# panel-8-touch-pad.net
KiCad netlist of a schematic drawn in Altium Designer
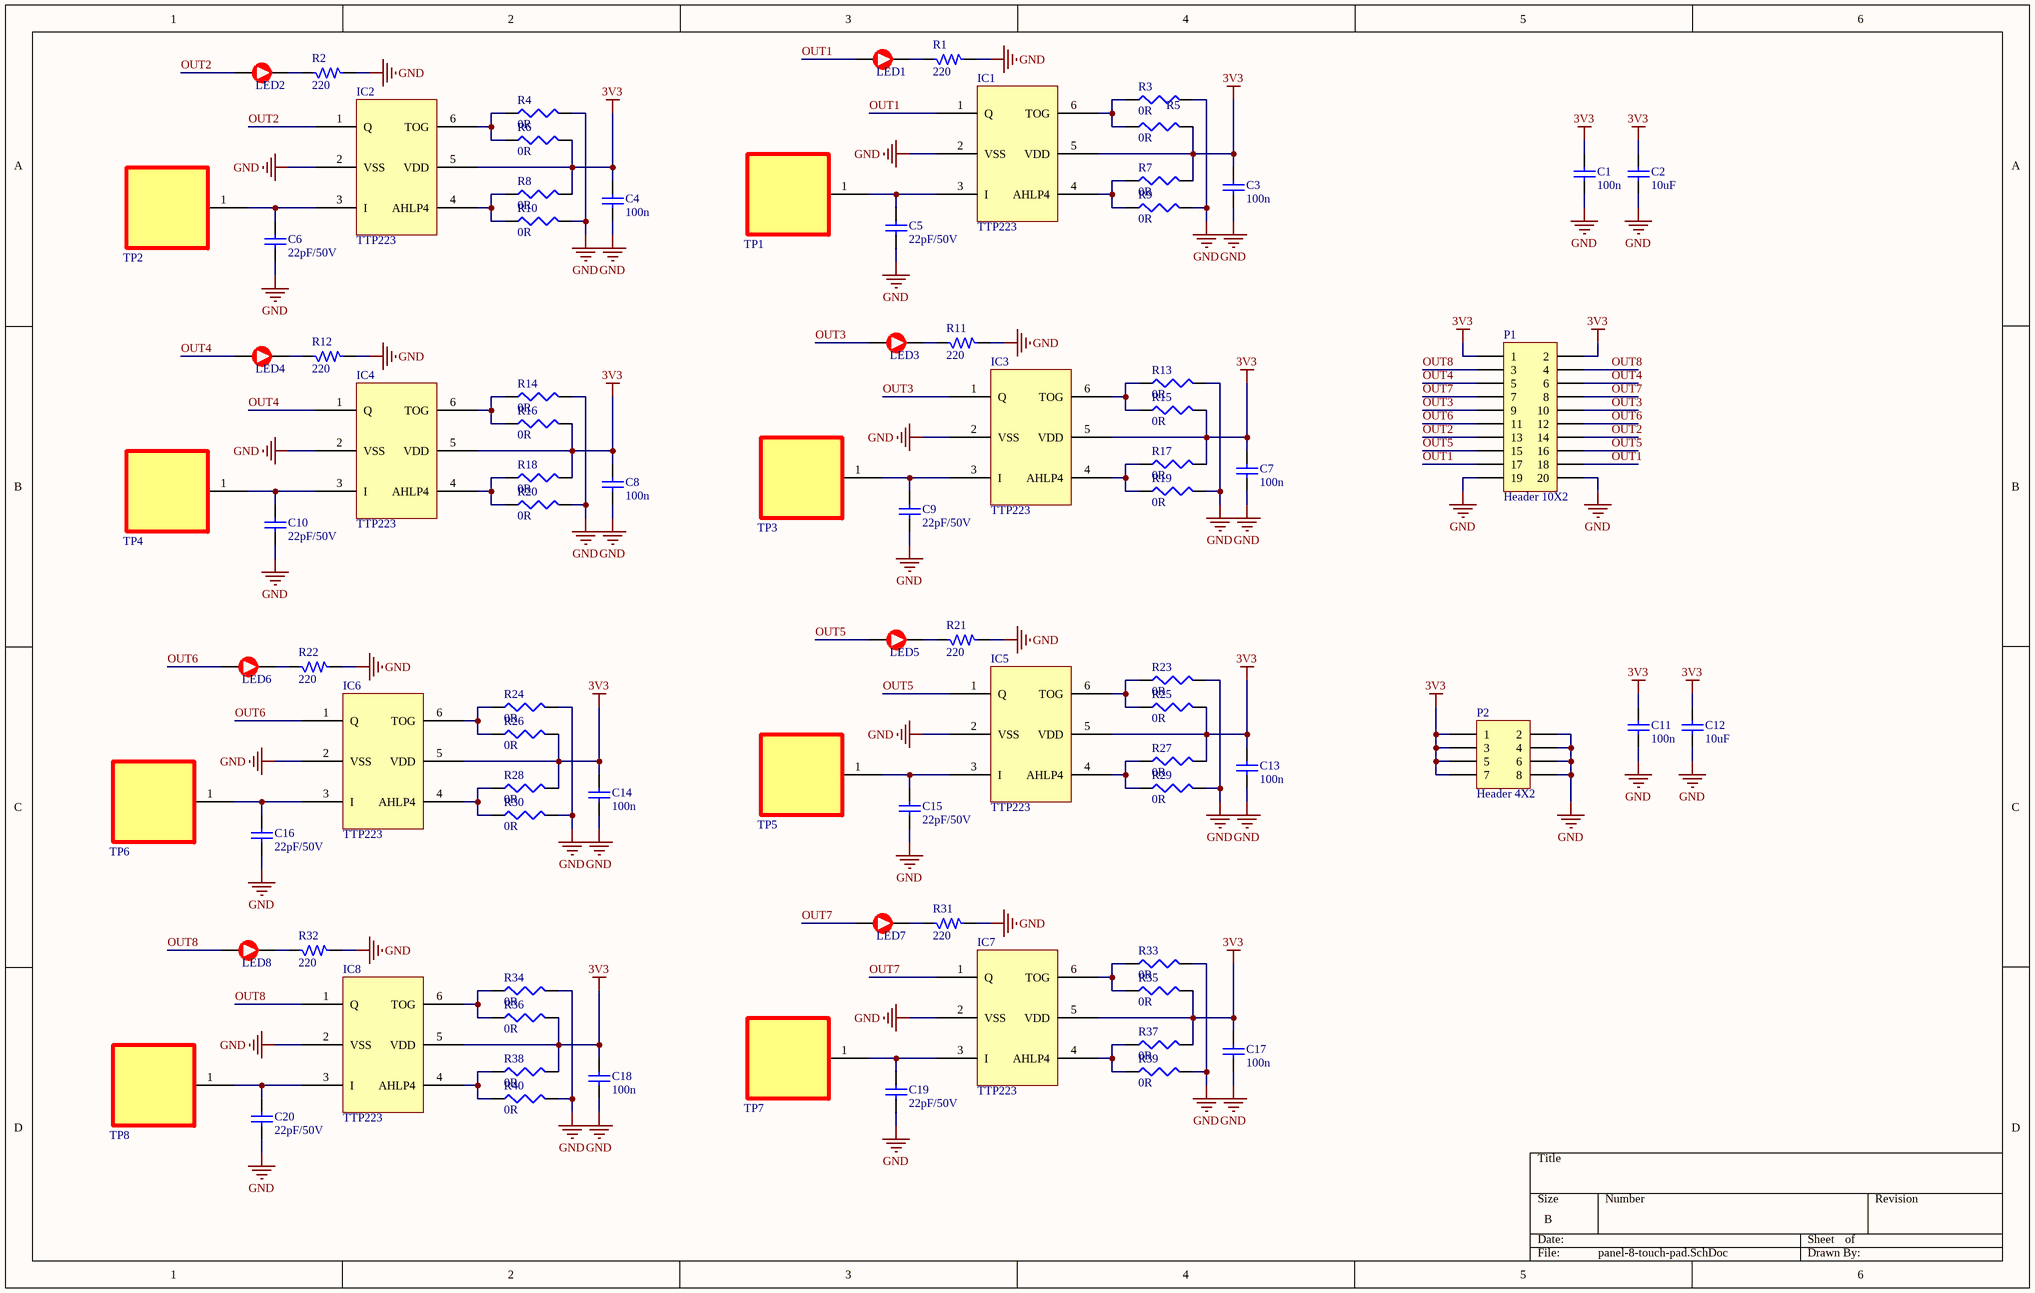
[diagram p0: panel-8-touch-pad.SchDoc]

(export (version "E")
  (design (tool "Eeschema 10.0.6"))
  (components
    (comp (ref "C1")
      (value "100n")
      (footprint "Capacitor:C0805")
      (description "Capacitor 100n 16V 0603")
      (fields (field (name "PUBLISHER") "Altium Limited"))
      (libsource (lib "Schlib1") (part "Cap Semi"))
    )
    (comp (ref "C2")
      (value "10uF")
      (footprint "Capacitor:C1206")
      (description "Capacitor 100n 16V 0603")
      (fields (field (name "PUBLISHER") "Altium Limited"))
      (libsource (lib "Schlib1") (part "Cap Semi"))
    )
    (comp (ref "C3")
      (value "100n")
      (footprint "Capacitor:C0805")
      (description "Capacitor 100n 16V 0603")
      (fields (field (name "PUBLISHER") "Altium Limited"))
      (libsource (lib "Schlib1") (part "Cap Semi"))
    )
    (comp (ref "C4")
      (value "100n")
      (footprint "Capacitor:C0805")
      (description "Capacitor 100n 16V 0603")
      (fields (field (name "PUBLISHER") "Altium Limited"))
      (libsource (lib "Schlib1") (part "Cap Semi"))
    )
    (comp (ref "C5")
      (value "22pF/50V")
      (footprint "Capacitor:C0805")
      (description "Capacitor 100n 16V 0603")
      (fields (field (name "PUBLISHER") "Altium Limited"))
      (libsource (lib "Schlib1") (part "Cap Semi"))
    )
    (comp (ref "C6")
      (value "22pF/50V")
      (footprint "Capacitor:C0805")
      (description "Capacitor 100n 16V 0603")
      (fields (field (name "PUBLISHER") "Altium Limited"))
      (libsource (lib "Schlib1") (part "Cap Semi"))
    )
    (comp (ref "C7")
      (value "100n")
      (footprint "Capacitor:C0805")
      (description "Capacitor 100n 16V 0603")
      (fields (field (name "PUBLISHER") "Altium Limited"))
      (libsource (lib "Schlib1") (part "Cap Semi"))
    )
    (comp (ref "C8")
      (value "100n")
      (footprint "Capacitor:C0805")
      (description "Capacitor 100n 16V 0603")
      (fields (field (name "PUBLISHER") "Altium Limited"))
      (libsource (lib "Schlib1") (part "Cap Semi"))
    )
    (comp (ref "C9")
      (value "22pF/50V")
      (footprint "Capacitor:C0805")
      (description "Capacitor 100n 16V 0603")
      (fields (field (name "PUBLISHER") "Altium Limited"))
      (libsource (lib "Schlib1") (part "Cap Semi"))
    )
    (comp (ref "C10")
      (value "22pF/50V")
      (footprint "Capacitor:C0805")
      (description "Capacitor 100n 16V 0603")
      (fields (field (name "PUBLISHER") "Altium Limited"))
      (libsource (lib "Schlib1") (part "Cap Semi"))
    )
    (comp (ref "C11")
      (value "100n")
      (footprint "Capacitor:C0805")
      (description "Capacitor 100n 16V 0603")
      (fields (field (name "PUBLISHER") "Altium Limited"))
      (libsource (lib "Schlib1") (part "Cap Semi"))
    )
    (comp (ref "C12")
      (value "10uF")
      (footprint "Capacitor:C1206")
      (description "Capacitor 100n 16V 0603")
      (fields (field (name "PUBLISHER") "Altium Limited"))
      (libsource (lib "Schlib1") (part "Cap Semi"))
    )
    (comp (ref "C13")
      (value "100n")
      (footprint "Capacitor:C0805")
      (description "Capacitor 100n 16V 0603")
      (fields (field (name "PUBLISHER") "Altium Limited"))
      (libsource (lib "Schlib1") (part "Cap Semi"))
    )
    (comp (ref "C14")
      (value "100n")
      (footprint "Capacitor:C0805")
      (description "Capacitor 100n 16V 0603")
      (fields (field (name "PUBLISHER") "Altium Limited"))
      (libsource (lib "Schlib1") (part "Cap Semi"))
    )
    (comp (ref "C15")
      (value "22pF/50V")
      (footprint "Capacitor:C0805")
      (description "Capacitor 100n 16V 0603")
      (fields (field (name "PUBLISHER") "Altium Limited"))
      (libsource (lib "Schlib1") (part "Cap Semi"))
    )
    (comp (ref "C16")
      (value "22pF/50V")
      (footprint "Capacitor:C0805")
      (description "Capacitor 100n 16V 0603")
      (fields (field (name "PUBLISHER") "Altium Limited"))
      (libsource (lib "Schlib1") (part "Cap Semi"))
    )
    (comp (ref "C17")
      (value "100n")
      (footprint "Capacitor:C0805")
      (description "Capacitor 100n 16V 0603")
      (fields (field (name "PUBLISHER") "Altium Limited"))
      (libsource (lib "Schlib1") (part "Cap Semi"))
    )
    (comp (ref "C18")
      (value "100n")
      (footprint "Capacitor:C0805")
      (description "Capacitor 100n 16V 0603")
      (fields (field (name "PUBLISHER") "Altium Limited"))
      (libsource (lib "Schlib1") (part "Cap Semi"))
    )
    (comp (ref "C19")
      (value "22pF/50V")
      (footprint "Capacitor:C0805")
      (description "Capacitor 100n 16V 0603")
      (fields (field (name "PUBLISHER") "Altium Limited"))
      (libsource (lib "Schlib1") (part "Cap Semi"))
    )
    (comp (ref "C20")
      (value "22pF/50V")
      (footprint "Capacitor:C0805")
      (description "Capacitor 100n 16V 0603")
      (fields (field (name "PUBLISHER") "Altium Limited"))
      (libsource (lib "Schlib1") (part "Cap Semi"))
    )
    (comp (ref "IC1")
      (value "TTP223")
      (footprint "Miscellaneous Devices:SOT23-6_L")
      (description "TTP223 Touch")
      (libsource (lib "touch-lib") (part "TTP223"))
    )
    (comp (ref "IC2")
      (value "TTP223")
      (footprint "Miscellaneous Devices:SOT23-6_L")
      (description "TTP223 Touch")
      (libsource (lib "touch-lib") (part "TTP223"))
    )
    (comp (ref "IC3")
      (value "TTP223")
      (footprint "Miscellaneous Devices:SOT23-6_L")
      (description "TTP223 Touch")
      (libsource (lib "touch-lib") (part "TTP223"))
    )
    (comp (ref "IC4")
      (value "TTP223")
      (footprint "Miscellaneous Devices:SOT23-6_L")
      (description "TTP223 Touch")
      (libsource (lib "touch-lib") (part "TTP223"))
    )
    (comp (ref "IC5")
      (value "TTP223")
      (footprint "Miscellaneous Devices:SOT23-6_L")
      (description "TTP223 Touch")
      (libsource (lib "touch-lib") (part "TTP223"))
    )
    (comp (ref "IC6")
      (value "TTP223")
      (footprint "Miscellaneous Devices:SOT23-6_L")
      (description "TTP223 Touch")
      (libsource (lib "touch-lib") (part "TTP223"))
    )
    (comp (ref "IC7")
      (value "TTP223")
      (footprint "Miscellaneous Devices:SOT23-6_L")
      (description "TTP223 Touch")
      (libsource (lib "touch-lib") (part "TTP223"))
    )
    (comp (ref "IC8")
      (value "TTP223")
      (footprint "Miscellaneous Devices:SOT23-6_L")
      (description "TTP223 Touch")
      (libsource (lib "touch-lib") (part "TTP223"))
    )
    (comp (ref "LED1")
      (value "led-lib:LED_0805_Blue")
      (footprint "led-lib:LED_0805_Blue")
      (description "LED")
      (fields (field (name "MANUFACTURER") "Harvatek"))
      (libsource (lib "SS_Basic") (part "Led"))
    )
    (comp (ref "LED2")
      (value "led-lib:LED_0805_Blue")
      (footprint "led-lib:LED_0805_Blue")
      (description "LED")
      (fields (field (name "MANUFACTURER") "Harvatek"))
      (libsource (lib "SS_Basic") (part "Led"))
    )
    (comp (ref "LED3")
      (value "led-lib:LED_0805_Blue")
      (footprint "led-lib:LED_0805_Blue")
      (description "LED")
      (fields (field (name "MANUFACTURER") "Harvatek"))
      (libsource (lib "SS_Basic") (part "Led"))
    )
    (comp (ref "LED4")
      (value "led-lib:LED_0805_Blue")
      (footprint "led-lib:LED_0805_Blue")
      (description "LED")
      (fields (field (name "MANUFACTURER") "Harvatek"))
      (libsource (lib "SS_Basic") (part "Led"))
    )
    (comp (ref "LED5")
      (value "led-lib:LED_0805_Blue")
      (footprint "led-lib:LED_0805_Blue")
      (description "LED")
      (fields (field (name "MANUFACTURER") "Harvatek"))
      (libsource (lib "SS_Basic") (part "Led"))
    )
    (comp (ref "LED6")
      (value "led-lib:LED_0805_Blue")
      (footprint "led-lib:LED_0805_Blue")
      (description "LED")
      (fields (field (name "MANUFACTURER") "Harvatek"))
      (libsource (lib "SS_Basic") (part "Led"))
    )
    (comp (ref "LED7")
      (value "led-lib:LED_0805_Blue")
      (footprint "led-lib:LED_0805_Blue")
      (description "LED")
      (fields (field (name "MANUFACTURER") "Harvatek"))
      (libsource (lib "SS_Basic") (part "Led"))
    )
    (comp (ref "LED8")
      (value "led-lib:LED_0805_Blue")
      (footprint "led-lib:LED_0805_Blue")
      (description "LED")
      (fields (field (name "MANUFACTURER") "Harvatek"))
      (libsource (lib "SS_Basic") (part "Led"))
    )
    (comp (ref "P1")
      (value "Header 10X2")
      (footprint "SS_Con:HDR2X10 - SMD - 2mm")
      (description "Header, 10-Pin, Dual row")
      (fields (field (name "PUBLISHER") "Altium Limited"))
      (libsource (lib "SS_Con") (part "Header 10X2"))
    )
    (comp (ref "P2")
      (value "Header 4X2")
      (footprint "SS_Con:HDR2X4 - SMD - 2mm")
      (description "Header, 4-Pin, Dual row")
      (fields (field (name "PUBLISHER") "Altium Limited"))
      (libsource (lib "SS_Con") (part "Header 4X2"))
    )
    (comp (ref "R1")
      (value "220")
      (footprint "R0805")
      (description "Resistor SMD")
      (fields (field (name "MANUFACTURER") "UniOhm"))
      (libsource (lib "Schlib1") (part "RM"))
    )
    (comp (ref "R2")
      (value "220")
      (footprint "R0805")
      (description "Resistor SMD")
      (fields (field (name "MANUFACTURER") "UniOhm"))
      (libsource (lib "Schlib1") (part "RM"))
    )
    (comp (ref "R3")
      (value "0R")
      (footprint "R0805")
      (description "Resistor 10k 0603")
      (fields (field (name "PUBLISHER") "Altium Limited"))
      (libsource (lib "Miscellaneous Devices") (part "Res3"))
    )
    (comp (ref "R4")
      (value "0R")
      (footprint "R0805")
      (description "Resistor 10k 0603")
      (fields (field (name "PUBLISHER") "Altium Limited"))
      (libsource (lib "Miscellaneous Devices") (part "Res3"))
    )
    (comp (ref "R5")
      (value "0R")
      (footprint "R0805")
      (description "Resistor 10k 0603")
      (fields (field (name "PUBLISHER") "Altium Limited"))
      (libsource (lib "Miscellaneous Devices") (part "Res3"))
    )
    (comp (ref "R6")
      (value "0R")
      (footprint "R0805")
      (description "Resistor 10k 0603")
      (fields (field (name "PUBLISHER") "Altium Limited"))
      (libsource (lib "Miscellaneous Devices") (part "Res3"))
    )
    (comp (ref "R7")
      (value "0R")
      (footprint "R0805")
      (description "Resistor 10k 0603")
      (fields (field (name "PUBLISHER") "Altium Limited"))
      (libsource (lib "Miscellaneous Devices") (part "Res3"))
    )
    (comp (ref "R8")
      (value "0R")
      (footprint "R0805")
      (description "Resistor 10k 0603")
      (fields (field (name "PUBLISHER") "Altium Limited"))
      (libsource (lib "Miscellaneous Devices") (part "Res3"))
    )
    (comp (ref "R9")
      (value "0R")
      (footprint "R0805")
      (description "Resistor 10k 0603")
      (fields (field (name "PUBLISHER") "Altium Limited"))
      (libsource (lib "Miscellaneous Devices") (part "Res3"))
    )
    (comp (ref "R10")
      (value "0R")
      (footprint "R0805")
      (description "Resistor 10k 0603")
      (fields (field (name "PUBLISHER") "Altium Limited"))
      (libsource (lib "Miscellaneous Devices") (part "Res3"))
    )
    (comp (ref "R11")
      (value "220")
      (footprint "R0805")
      (description "Resistor SMD")
      (fields (field (name "MANUFACTURER") "UniOhm"))
      (libsource (lib "Schlib1") (part "RM"))
    )
    (comp (ref "R12")
      (value "220")
      (footprint "R0805")
      (description "Resistor SMD")
      (fields (field (name "MANUFACTURER") "UniOhm"))
      (libsource (lib "Schlib1") (part "RM"))
    )
    (comp (ref "R13")
      (value "0R")
      (footprint "R0805")
      (description "Resistor 10k 0603")
      (fields (field (name "PUBLISHER") "Altium Limited"))
      (libsource (lib "Miscellaneous Devices") (part "Res3"))
    )
    (comp (ref "R14")
      (value "0R")
      (footprint "R0805")
      (description "Resistor 10k 0603")
      (fields (field (name "PUBLISHER") "Altium Limited"))
      (libsource (lib "Miscellaneous Devices") (part "Res3"))
    )
    (comp (ref "R15")
      (value "0R")
      (footprint "R0805")
      (description "Resistor 10k 0603")
      (fields (field (name "PUBLISHER") "Altium Limited"))
      (libsource (lib "Miscellaneous Devices") (part "Res3"))
    )
    (comp (ref "R16")
      (value "0R")
      (footprint "R0805")
      (description "Resistor 10k 0603")
      (fields (field (name "PUBLISHER") "Altium Limited"))
      (libsource (lib "Miscellaneous Devices") (part "Res3"))
    )
    (comp (ref "R17")
      (value "0R")
      (footprint "R0805")
      (description "Resistor 10k 0603")
      (fields (field (name "PUBLISHER") "Altium Limited"))
      (libsource (lib "Miscellaneous Devices") (part "Res3"))
    )
    (comp (ref "R18")
      (value "0R")
      (footprint "R0805")
      (description "Resistor 10k 0603")
      (fields (field (name "PUBLISHER") "Altium Limited"))
      (libsource (lib "Miscellaneous Devices") (part "Res3"))
    )
    (comp (ref "R19")
      (value "0R")
      (footprint "R0805")
      (description "Resistor 10k 0603")
      (fields (field (name "PUBLISHER") "Altium Limited"))
      (libsource (lib "Miscellaneous Devices") (part "Res3"))
    )
    (comp (ref "R20")
      (value "0R")
      (footprint "R0805")
      (description "Resistor 10k 0603")
      (fields (field (name "PUBLISHER") "Altium Limited"))
      (libsource (lib "Miscellaneous Devices") (part "Res3"))
    )
    (comp (ref "R21")
      (value "220")
      (footprint "R0805")
      (description "Resistor SMD")
      (fields (field (name "MANUFACTURER") "UniOhm"))
      (libsource (lib "Schlib1") (part "RM"))
    )
    (comp (ref "R22")
      (value "220")
      (footprint "R0805")
      (description "Resistor SMD")
      (fields (field (name "MANUFACTURER") "UniOhm"))
      (libsource (lib "Schlib1") (part "RM"))
    )
    (comp (ref "R23")
      (value "0R")
      (footprint "R0805")
      (description "Resistor 10k 0603")
      (fields (field (name "PUBLISHER") "Altium Limited"))
      (libsource (lib "Miscellaneous Devices") (part "Res3"))
    )
    (comp (ref "R24")
      (value "0R")
      (footprint "R0805")
      (description "Resistor 10k 0603")
      (fields (field (name "PUBLISHER") "Altium Limited"))
      (libsource (lib "Miscellaneous Devices") (part "Res3"))
    )
    (comp (ref "R25")
      (value "0R")
      (footprint "R0805")
      (description "Resistor 10k 0603")
      (fields (field (name "PUBLISHER") "Altium Limited"))
      (libsource (lib "Miscellaneous Devices") (part "Res3"))
    )
    (comp (ref "R26")
      (value "0R")
      (footprint "R0805")
      (description "Resistor 10k 0603")
      (fields (field (name "PUBLISHER") "Altium Limited"))
      (libsource (lib "Miscellaneous Devices") (part "Res3"))
    )
    (comp (ref "R27")
      (value "0R")
      (footprint "R0805")
      (description "Resistor 10k 0603")
      (fields (field (name "PUBLISHER") "Altium Limited"))
      (libsource (lib "Miscellaneous Devices") (part "Res3"))
    )
    (comp (ref "R28")
      (value "0R")
      (footprint "R0805")
      (description "Resistor 10k 0603")
      (fields (field (name "PUBLISHER") "Altium Limited"))
      (libsource (lib "Miscellaneous Devices") (part "Res3"))
    )
    (comp (ref "R29")
      (value "0R")
      (footprint "R0805")
      (description "Resistor 10k 0603")
      (fields (field (name "PUBLISHER") "Altium Limited"))
      (libsource (lib "Miscellaneous Devices") (part "Res3"))
    )
    (comp (ref "R30")
      (value "0R")
      (footprint "R0805")
      (description "Resistor 10k 0603")
      (fields (field (name "PUBLISHER") "Altium Limited"))
      (libsource (lib "Miscellaneous Devices") (part "Res3"))
    )
    (comp (ref "R31")
      (value "220")
      (footprint "R0805")
      (description "Resistor SMD")
      (fields (field (name "MANUFACTURER") "UniOhm"))
      (libsource (lib "Schlib1") (part "RM"))
    )
    (comp (ref "R32")
      (value "220")
      (footprint "R0805")
      (description "Resistor SMD")
      (fields (field (name "MANUFACTURER") "UniOhm"))
      (libsource (lib "Schlib1") (part "RM"))
    )
    (comp (ref "R33")
      (value "0R")
      (footprint "R0805")
      (description "Resistor 10k 0603")
      (fields (field (name "PUBLISHER") "Altium Limited"))
      (libsource (lib "Miscellaneous Devices") (part "Res3"))
    )
    (comp (ref "R34")
      (value "0R")
      (footprint "R0805")
      (description "Resistor 10k 0603")
      (fields (field (name "PUBLISHER") "Altium Limited"))
      (libsource (lib "Miscellaneous Devices") (part "Res3"))
    )
    (comp (ref "R35")
      (value "0R")
      (footprint "R0805")
      (description "Resistor 10k 0603")
      (fields (field (name "PUBLISHER") "Altium Limited"))
      (libsource (lib "Miscellaneous Devices") (part "Res3"))
    )
    (comp (ref "R36")
      (value "0R")
      (footprint "R0805")
      (description "Resistor 10k 0603")
      (fields (field (name "PUBLISHER") "Altium Limited"))
      (libsource (lib "Miscellaneous Devices") (part "Res3"))
    )
    (comp (ref "R37")
      (value "0R")
      (footprint "R0805")
      (description "Resistor 10k 0603")
      (fields (field (name "PUBLISHER") "Altium Limited"))
      (libsource (lib "Miscellaneous Devices") (part "Res3"))
    )
    (comp (ref "R38")
      (value "0R")
      (footprint "R0805")
      (description "Resistor 10k 0603")
      (fields (field (name "PUBLISHER") "Altium Limited"))
      (libsource (lib "Miscellaneous Devices") (part "Res3"))
    )
    (comp (ref "R39")
      (value "0R")
      (footprint "R0805")
      (description "Resistor 10k 0603")
      (fields (field (name "PUBLISHER") "Altium Limited"))
      (libsource (lib "Miscellaneous Devices") (part "Res3"))
    )
    (comp (ref "R40")
      (value "0R")
      (footprint "R0805")
      (description "Resistor 10k 0603")
      (fields (field (name "PUBLISHER") "Altium Limited"))
      (libsource (lib "Miscellaneous Devices") (part "Res3"))
    )
    (comp (ref "TP1")
      (value "TP")
      (footprint "Touch-Pad-Rec")
      (description "Touch Pad")
      (libsource (lib "touch-lib") (part "Touch-Pad"))
    )
    (comp (ref "TP2")
      (value "TP")
      (footprint "Touch-Pad-Rec")
      (description "Touch Pad")
      (libsource (lib "touch-lib") (part "Touch-Pad"))
    )
    (comp (ref "TP3")
      (value "TP")
      (footprint "Touch-Pad-Rec")
      (description "Touch Pad")
      (libsource (lib "touch-lib") (part "Touch-Pad"))
    )
    (comp (ref "TP4")
      (value "TP")
      (footprint "Touch-Pad-Rec")
      (description "Touch Pad")
      (libsource (lib "touch-lib") (part "Touch-Pad"))
    )
    (comp (ref "TP5")
      (value "TP")
      (footprint "Touch-Pad-Rec")
      (description "Touch Pad")
      (libsource (lib "touch-lib") (part "Touch-Pad"))
    )
    (comp (ref "TP6")
      (value "TP")
      (footprint "Touch-Pad-Rec")
      (description "Touch Pad")
      (libsource (lib "touch-lib") (part "Touch-Pad"))
    )
    (comp (ref "TP7")
      (value "TP")
      (footprint "Touch-Pad-Rec")
      (description "Touch Pad")
      (libsource (lib "touch-lib") (part "Touch-Pad"))
    )
    (comp (ref "TP8")
      (value "TP")
      (footprint "Touch-Pad-Rec")
      (description "Touch Pad")
      (libsource (lib "touch-lib") (part "Touch-Pad"))
    )
  )
  (nets
    (net (code "1") (name "/OUT1") (class "Default")
      (node (ref "IC1") (pin "1") (pinfunction "Q_1") (pintype "passive"))
      (node (ref "LED1") (pin "2") (pinfunction "2_2") (pintype "passive"))
      (node (ref "P1") (pin "17") (pinfunction "17_17") (pintype "passive"))
      (node (ref "P1") (pin "18") (pinfunction "18_18") (pintype "passive"))
    )
    (net (code "2") (name "/OUT2") (class "Default")
      (node (ref "IC2") (pin "1") (pinfunction "Q_1") (pintype "passive"))
      (node (ref "LED2") (pin "2") (pinfunction "2_2") (pintype "passive"))
      (node (ref "P1") (pin "13") (pinfunction "13_13") (pintype "passive"))
      (node (ref "P1") (pin "14") (pinfunction "14_14") (pintype "passive"))
    )
    (net (code "3") (name "/OUT3") (class "Default")
      (node (ref "IC3") (pin "1") (pinfunction "Q_1") (pintype "passive"))
      (node (ref "LED3") (pin "2") (pinfunction "2_2") (pintype "passive"))
      (node (ref "P1") (pin "10") (pinfunction "10_10") (pintype "passive"))
      (node (ref "P1") (pin "9") (pinfunction "9_9") (pintype "passive"))
    )
    (net (code "4") (name "/OUT4") (class "Default")
      (node (ref "IC4") (pin "1") (pinfunction "Q_1") (pintype "passive"))
      (node (ref "LED4") (pin "2") (pinfunction "2_2") (pintype "passive"))
      (node (ref "P1") (pin "5") (pinfunction "5_5") (pintype "passive"))
      (node (ref "P1") (pin "6") (pinfunction "6_6") (pintype "passive"))
    )
    (net (code "5") (name "/OUT5") (class "Default")
      (node (ref "IC5") (pin "1") (pinfunction "Q_1") (pintype "passive"))
      (node (ref "LED5") (pin "2") (pinfunction "2_2") (pintype "passive"))
      (node (ref "P1") (pin "15") (pinfunction "15_15") (pintype "passive"))
      (node (ref "P1") (pin "16") (pinfunction "16_16") (pintype "passive"))
    )
    (net (code "6") (name "/OUT6") (class "Default")
      (node (ref "IC6") (pin "1") (pinfunction "Q_1") (pintype "passive"))
      (node (ref "LED6") (pin "2") (pinfunction "2_2") (pintype "passive"))
      (node (ref "P1") (pin "11") (pinfunction "11_11") (pintype "passive"))
      (node (ref "P1") (pin "12") (pinfunction "12_12") (pintype "passive"))
    )
    (net (code "7") (name "/OUT7") (class "Default")
      (node (ref "IC7") (pin "1") (pinfunction "Q_1") (pintype "passive"))
      (node (ref "LED7") (pin "2") (pinfunction "2_2") (pintype "passive"))
      (node (ref "P1") (pin "7") (pinfunction "7_7") (pintype "passive"))
      (node (ref "P1") (pin "8") (pinfunction "8_8") (pintype "passive"))
    )
    (net (code "8") (name "/OUT8") (class "Default")
      (node (ref "IC8") (pin "1") (pinfunction "Q_1") (pintype "passive"))
      (node (ref "LED8") (pin "2") (pinfunction "2_2") (pintype "passive"))
      (node (ref "P1") (pin "3") (pinfunction "3_3") (pintype "passive"))
      (node (ref "P1") (pin "4") (pinfunction "4_4") (pintype "passive"))
    )
    (net (code "9") (name "3V3") (class "Default")
      (node (ref "C1") (pin "1") (pinfunction "1_1") (pintype "passive"))
      (node (ref "C11") (pin "1") (pinfunction "1_1") (pintype "passive"))
      (node (ref "C12") (pin "1") (pinfunction "1_1") (pintype "passive"))
      (node (ref "C13") (pin "1") (pinfunction "1_1") (pintype "passive"))
      (node (ref "C14") (pin "1") (pinfunction "1_1") (pintype "passive"))
      (node (ref "C17") (pin "1") (pinfunction "1_1") (pintype "passive"))
      (node (ref "C18") (pin "1") (pinfunction "1_1") (pintype "passive"))
      (node (ref "C2") (pin "1") (pinfunction "1_1") (pintype "passive"))
      (node (ref "C3") (pin "1") (pinfunction "1_1") (pintype "passive"))
      (node (ref "C4") (pin "1") (pinfunction "1_1") (pintype "passive"))
      (node (ref "C7") (pin "1") (pinfunction "1_1") (pintype "passive"))
      (node (ref "C8") (pin "1") (pinfunction "1_1") (pintype "passive"))
      (node (ref "IC1") (pin "5") (pinfunction "VDD_5") (pintype "passive"))
      (node (ref "IC2") (pin "5") (pinfunction "VDD_5") (pintype "passive"))
      (node (ref "IC3") (pin "5") (pinfunction "VDD_5") (pintype "passive"))
      (node (ref "IC4") (pin "5") (pinfunction "VDD_5") (pintype "passive"))
      (node (ref "IC5") (pin "5") (pinfunction "VDD_5") (pintype "passive"))
      (node (ref "IC6") (pin "5") (pinfunction "VDD_5") (pintype "passive"))
      (node (ref "IC7") (pin "5") (pinfunction "VDD_5") (pintype "passive"))
      (node (ref "IC8") (pin "5") (pinfunction "VDD_5") (pintype "passive"))
      (node (ref "P1") (pin "1") (pinfunction "1_1") (pintype "passive"))
      (node (ref "P1") (pin "2") (pinfunction "2_2") (pintype "passive"))
      (node (ref "P2") (pin "1") (pinfunction "1_1") (pintype "passive"))
      (node (ref "P2") (pin "3") (pinfunction "3_3") (pintype "passive"))
      (node (ref "P2") (pin "5") (pinfunction "5_5") (pintype "passive"))
      (node (ref "P2") (pin "7") (pinfunction "7_7") (pintype "passive"))
      (node (ref "R15") (pin "2") (pinfunction "2_2") (pintype "passive"))
      (node (ref "R16") (pin "2") (pinfunction "2_2") (pintype "passive"))
      (node (ref "R17") (pin "2") (pinfunction "2_2") (pintype "passive"))
      (node (ref "R18") (pin "2") (pinfunction "2_2") (pintype "passive"))
      (node (ref "R25") (pin "2") (pinfunction "2_2") (pintype "passive"))
      (node (ref "R26") (pin "2") (pinfunction "2_2") (pintype "passive"))
      (node (ref "R27") (pin "2") (pinfunction "2_2") (pintype "passive"))
      (node (ref "R28") (pin "2") (pinfunction "2_2") (pintype "passive"))
      (node (ref "R35") (pin "2") (pinfunction "2_2") (pintype "passive"))
      (node (ref "R36") (pin "2") (pinfunction "2_2") (pintype "passive"))
      (node (ref "R37") (pin "2") (pinfunction "2_2") (pintype "passive"))
      (node (ref "R38") (pin "2") (pinfunction "2_2") (pintype "passive"))
      (node (ref "R5") (pin "2") (pinfunction "2_2") (pintype "passive"))
      (node (ref "R6") (pin "2") (pinfunction "2_2") (pintype "passive"))
      (node (ref "R7") (pin "2") (pinfunction "2_2") (pintype "passive"))
      (node (ref "R8") (pin "2") (pinfunction "2_2") (pintype "passive"))
    )
    (net (code "10") (name "GND") (class "Default")
      (node (ref "C1") (pin "2") (pinfunction "2_2") (pintype "passive"))
      (node (ref "C10") (pin "2") (pinfunction "2_2") (pintype "passive"))
      (node (ref "C11") (pin "2") (pinfunction "2_2") (pintype "passive"))
      (node (ref "C12") (pin "2") (pinfunction "2_2") (pintype "passive"))
      (node (ref "C13") (pin "2") (pinfunction "2_2") (pintype "passive"))
      (node (ref "C14") (pin "2") (pinfunction "2_2") (pintype "passive"))
      (node (ref "C15") (pin "2") (pinfunction "2_2") (pintype "passive"))
      (node (ref "C16") (pin "2") (pinfunction "2_2") (pintype "passive"))
      (node (ref "C17") (pin "2") (pinfunction "2_2") (pintype "passive"))
      (node (ref "C18") (pin "2") (pinfunction "2_2") (pintype "passive"))
      (node (ref "C19") (pin "2") (pinfunction "2_2") (pintype "passive"))
      (node (ref "C2") (pin "2") (pinfunction "2_2") (pintype "passive"))
      (node (ref "C20") (pin "2") (pinfunction "2_2") (pintype "passive"))
      (node (ref "C3") (pin "2") (pinfunction "2_2") (pintype "passive"))
      (node (ref "C4") (pin "2") (pinfunction "2_2") (pintype "passive"))
      (node (ref "C5") (pin "2") (pinfunction "2_2") (pintype "passive"))
      (node (ref "C6") (pin "2") (pinfunction "2_2") (pintype "passive"))
      (node (ref "C7") (pin "2") (pinfunction "2_2") (pintype "passive"))
      (node (ref "C8") (pin "2") (pinfunction "2_2") (pintype "passive"))
      (node (ref "C9") (pin "2") (pinfunction "2_2") (pintype "passive"))
      (node (ref "IC1") (pin "2") (pinfunction "VSS_2") (pintype "passive"))
      (node (ref "IC2") (pin "2") (pinfunction "VSS_2") (pintype "passive"))
      (node (ref "IC3") (pin "2") (pinfunction "VSS_2") (pintype "passive"))
      (node (ref "IC4") (pin "2") (pinfunction "VSS_2") (pintype "passive"))
      (node (ref "IC5") (pin "2") (pinfunction "VSS_2") (pintype "passive"))
      (node (ref "IC6") (pin "2") (pinfunction "VSS_2") (pintype "passive"))
      (node (ref "IC7") (pin "2") (pinfunction "VSS_2") (pintype "passive"))
      (node (ref "IC8") (pin "2") (pinfunction "VSS_2") (pintype "passive"))
      (node (ref "P1") (pin "19") (pinfunction "19_19") (pintype "passive"))
      (node (ref "P1") (pin "20") (pinfunction "20_20") (pintype "passive"))
      (node (ref "P2") (pin "2") (pinfunction "2_2") (pintype "passive"))
      (node (ref "P2") (pin "4") (pinfunction "4_4") (pintype "passive"))
      (node (ref "P2") (pin "6") (pinfunction "6_6") (pintype "passive"))
      (node (ref "P2") (pin "8") (pinfunction "8_8") (pintype "passive"))
      (node (ref "R1") (pin "2") (pinfunction "2_2") (pintype "passive"))
      (node (ref "R10") (pin "2") (pinfunction "2_2") (pintype "passive"))
      (node (ref "R11") (pin "2") (pinfunction "2_2") (pintype "passive"))
      (node (ref "R12") (pin "2") (pinfunction "2_2") (pintype "passive"))
      (node (ref "R13") (pin "2") (pinfunction "2_2") (pintype "passive"))
      (node (ref "R14") (pin "2") (pinfunction "2_2") (pintype "passive"))
      (node (ref "R19") (pin "2") (pinfunction "2_2") (pintype "passive"))
      (node (ref "R2") (pin "2") (pinfunction "2_2") (pintype "passive"))
      (node (ref "R20") (pin "2") (pinfunction "2_2") (pintype "passive"))
      (node (ref "R21") (pin "2") (pinfunction "2_2") (pintype "passive"))
      (node (ref "R22") (pin "2") (pinfunction "2_2") (pintype "passive"))
      (node (ref "R23") (pin "2") (pinfunction "2_2") (pintype "passive"))
      (node (ref "R24") (pin "2") (pinfunction "2_2") (pintype "passive"))
      (node (ref "R29") (pin "2") (pinfunction "2_2") (pintype "passive"))
      (node (ref "R3") (pin "2") (pinfunction "2_2") (pintype "passive"))
      (node (ref "R30") (pin "2") (pinfunction "2_2") (pintype "passive"))
      (node (ref "R31") (pin "2") (pinfunction "2_2") (pintype "passive"))
      (node (ref "R32") (pin "2") (pinfunction "2_2") (pintype "passive"))
      (node (ref "R33") (pin "2") (pinfunction "2_2") (pintype "passive"))
      (node (ref "R34") (pin "2") (pinfunction "2_2") (pintype "passive"))
      (node (ref "R39") (pin "2") (pinfunction "2_2") (pintype "passive"))
      (node (ref "R4") (pin "2") (pinfunction "2_2") (pintype "passive"))
      (node (ref "R40") (pin "2") (pinfunction "2_2") (pintype "passive"))
      (node (ref "R9") (pin "2") (pinfunction "2_2") (pintype "passive"))
    )
    (net (code "11") (name "Net-(IC1-AHLP4)") (class "Default")
      (node (ref "IC1") (pin "4") (pinfunction "AHLP4_4") (pintype "passive"))
      (node (ref "R7") (pin "1") (pinfunction "1_1") (pintype "passive"))
      (node (ref "R9") (pin "1") (pinfunction "1_1") (pintype "passive"))
    )
    (net (code "12") (name "Net-(IC1-I)") (class "Default")
      (node (ref "C5") (pin "1") (pinfunction "1_1") (pintype "passive"))
      (node (ref "IC1") (pin "3") (pinfunction "I_3") (pintype "passive"))
      (node (ref "TP1") (pin "1") (pinfunction "1_1") (pintype "passive"))
    )
    (net (code "13") (name "Net-(IC1-TOG)") (class "Default")
      (node (ref "IC1") (pin "6") (pinfunction "TOG_6") (pintype "passive"))
      (node (ref "R3") (pin "1") (pinfunction "1_1") (pintype "passive"))
      (node (ref "R5") (pin "1") (pinfunction "1_1") (pintype "passive"))
    )
    (net (code "14") (name "Net-(IC2-AHLP4)") (class "Default")
      (node (ref "IC2") (pin "4") (pinfunction "AHLP4_4") (pintype "passive"))
      (node (ref "R10") (pin "1") (pinfunction "1_1") (pintype "passive"))
      (node (ref "R8") (pin "1") (pinfunction "1_1") (pintype "passive"))
    )
    (net (code "15") (name "Net-(IC2-I)") (class "Default")
      (node (ref "C6") (pin "1") (pinfunction "1_1") (pintype "passive"))
      (node (ref "IC2") (pin "3") (pinfunction "I_3") (pintype "passive"))
      (node (ref "TP2") (pin "1") (pinfunction "1_1") (pintype "passive"))
    )
    (net (code "16") (name "Net-(IC2-TOG)") (class "Default")
      (node (ref "IC2") (pin "6") (pinfunction "TOG_6") (pintype "passive"))
      (node (ref "R4") (pin "1") (pinfunction "1_1") (pintype "passive"))
      (node (ref "R6") (pin "1") (pinfunction "1_1") (pintype "passive"))
    )
    (net (code "17") (name "Net-(IC3-AHLP4)") (class "Default")
      (node (ref "IC3") (pin "4") (pinfunction "AHLP4_4") (pintype "passive"))
      (node (ref "R17") (pin "1") (pinfunction "1_1") (pintype "passive"))
      (node (ref "R19") (pin "1") (pinfunction "1_1") (pintype "passive"))
    )
    (net (code "18") (name "Net-(IC3-I)") (class "Default")
      (node (ref "C9") (pin "1") (pinfunction "1_1") (pintype "passive"))
      (node (ref "IC3") (pin "3") (pinfunction "I_3") (pintype "passive"))
      (node (ref "TP3") (pin "1") (pinfunction "1_1") (pintype "passive"))
    )
    (net (code "19") (name "Net-(IC3-TOG)") (class "Default")
      (node (ref "IC3") (pin "6") (pinfunction "TOG_6") (pintype "passive"))
      (node (ref "R13") (pin "1") (pinfunction "1_1") (pintype "passive"))
      (node (ref "R15") (pin "1") (pinfunction "1_1") (pintype "passive"))
    )
    (net (code "20") (name "Net-(IC4-AHLP4)") (class "Default")
      (node (ref "IC4") (pin "4") (pinfunction "AHLP4_4") (pintype "passive"))
      (node (ref "R18") (pin "1") (pinfunction "1_1") (pintype "passive"))
      (node (ref "R20") (pin "1") (pinfunction "1_1") (pintype "passive"))
    )
    (net (code "21") (name "Net-(IC4-I)") (class "Default")
      (node (ref "C10") (pin "1") (pinfunction "1_1") (pintype "passive"))
      (node (ref "IC4") (pin "3") (pinfunction "I_3") (pintype "passive"))
      (node (ref "TP4") (pin "1") (pinfunction "1_1") (pintype "passive"))
    )
    (net (code "22") (name "Net-(IC4-TOG)") (class "Default")
      (node (ref "IC4") (pin "6") (pinfunction "TOG_6") (pintype "passive"))
      (node (ref "R14") (pin "1") (pinfunction "1_1") (pintype "passive"))
      (node (ref "R16") (pin "1") (pinfunction "1_1") (pintype "passive"))
    )
    (net (code "23") (name "Net-(IC5-AHLP4)") (class "Default")
      (node (ref "IC5") (pin "4") (pinfunction "AHLP4_4") (pintype "passive"))
      (node (ref "R27") (pin "1") (pinfunction "1_1") (pintype "passive"))
      (node (ref "R29") (pin "1") (pinfunction "1_1") (pintype "passive"))
    )
    (net (code "24") (name "Net-(IC5-I)") (class "Default")
      (node (ref "C15") (pin "1") (pinfunction "1_1") (pintype "passive"))
      (node (ref "IC5") (pin "3") (pinfunction "I_3") (pintype "passive"))
      (node (ref "TP5") (pin "1") (pinfunction "1_1") (pintype "passive"))
    )
    (net (code "25") (name "Net-(IC5-TOG)") (class "Default")
      (node (ref "IC5") (pin "6") (pinfunction "TOG_6") (pintype "passive"))
      (node (ref "R23") (pin "1") (pinfunction "1_1") (pintype "passive"))
      (node (ref "R25") (pin "1") (pinfunction "1_1") (pintype "passive"))
    )
    (net (code "26") (name "Net-(IC6-AHLP4)") (class "Default")
      (node (ref "IC6") (pin "4") (pinfunction "AHLP4_4") (pintype "passive"))
      (node (ref "R28") (pin "1") (pinfunction "1_1") (pintype "passive"))
      (node (ref "R30") (pin "1") (pinfunction "1_1") (pintype "passive"))
    )
    (net (code "27") (name "Net-(IC6-I)") (class "Default")
      (node (ref "C16") (pin "1") (pinfunction "1_1") (pintype "passive"))
      (node (ref "IC6") (pin "3") (pinfunction "I_3") (pintype "passive"))
      (node (ref "TP6") (pin "1") (pinfunction "1_1") (pintype "passive"))
    )
    (net (code "28") (name "Net-(IC6-TOG)") (class "Default")
      (node (ref "IC6") (pin "6") (pinfunction "TOG_6") (pintype "passive"))
      (node (ref "R24") (pin "1") (pinfunction "1_1") (pintype "passive"))
      (node (ref "R26") (pin "1") (pinfunction "1_1") (pintype "passive"))
    )
    (net (code "29") (name "Net-(IC7-AHLP4)") (class "Default")
      (node (ref "IC7") (pin "4") (pinfunction "AHLP4_4") (pintype "passive"))
      (node (ref "R37") (pin "1") (pinfunction "1_1") (pintype "passive"))
      (node (ref "R39") (pin "1") (pinfunction "1_1") (pintype "passive"))
    )
    (net (code "30") (name "Net-(IC7-I)") (class "Default")
      (node (ref "C19") (pin "1") (pinfunction "1_1") (pintype "passive"))
      (node (ref "IC7") (pin "3") (pinfunction "I_3") (pintype "passive"))
      (node (ref "TP7") (pin "1") (pinfunction "1_1") (pintype "passive"))
    )
    (net (code "31") (name "Net-(IC7-TOG)") (class "Default")
      (node (ref "IC7") (pin "6") (pinfunction "TOG_6") (pintype "passive"))
      (node (ref "R33") (pin "1") (pinfunction "1_1") (pintype "passive"))
      (node (ref "R35") (pin "1") (pinfunction "1_1") (pintype "passive"))
    )
    (net (code "32") (name "Net-(IC8-AHLP4)") (class "Default")
      (node (ref "IC8") (pin "4") (pinfunction "AHLP4_4") (pintype "passive"))
      (node (ref "R38") (pin "1") (pinfunction "1_1") (pintype "passive"))
      (node (ref "R40") (pin "1") (pinfunction "1_1") (pintype "passive"))
    )
    (net (code "33") (name "Net-(IC8-I)") (class "Default")
      (node (ref "C20") (pin "1") (pinfunction "1_1") (pintype "passive"))
      (node (ref "IC8") (pin "3") (pinfunction "I_3") (pintype "passive"))
      (node (ref "TP8") (pin "1") (pinfunction "1_1") (pintype "passive"))
    )
    (net (code "34") (name "Net-(IC8-TOG)") (class "Default")
      (node (ref "IC8") (pin "6") (pinfunction "TOG_6") (pintype "passive"))
      (node (ref "R34") (pin "1") (pinfunction "1_1") (pintype "passive"))
      (node (ref "R36") (pin "1") (pinfunction "1_1") (pintype "passive"))
    )
    (net (code "35") (name "Net-(LED1-Pad1)") (class "Default")
      (node (ref "LED1") (pin "1") (pinfunction "1_1") (pintype "passive"))
      (node (ref "R1") (pin "1") (pinfunction "1_1") (pintype "passive"))
    )
    (net (code "36") (name "Net-(LED2-Pad1)") (class "Default")
      (node (ref "LED2") (pin "1") (pinfunction "1_1") (pintype "passive"))
      (node (ref "R2") (pin "1") (pinfunction "1_1") (pintype "passive"))
    )
    (net (code "37") (name "Net-(LED3-Pad1)") (class "Default")
      (node (ref "LED3") (pin "1") (pinfunction "1_1") (pintype "passive"))
      (node (ref "R11") (pin "1") (pinfunction "1_1") (pintype "passive"))
    )
    (net (code "38") (name "Net-(LED4-Pad1)") (class "Default")
      (node (ref "LED4") (pin "1") (pinfunction "1_1") (pintype "passive"))
      (node (ref "R12") (pin "1") (pinfunction "1_1") (pintype "passive"))
    )
    (net (code "39") (name "Net-(LED5-Pad1)") (class "Default")
      (node (ref "LED5") (pin "1") (pinfunction "1_1") (pintype "passive"))
      (node (ref "R21") (pin "1") (pinfunction "1_1") (pintype "passive"))
    )
    (net (code "40") (name "Net-(LED6-Pad1)") (class "Default")
      (node (ref "LED6") (pin "1") (pinfunction "1_1") (pintype "passive"))
      (node (ref "R22") (pin "1") (pinfunction "1_1") (pintype "passive"))
    )
    (net (code "41") (name "Net-(LED7-Pad1)") (class "Default")
      (node (ref "LED7") (pin "1") (pinfunction "1_1") (pintype "passive"))
      (node (ref "R31") (pin "1") (pinfunction "1_1") (pintype "passive"))
    )
    (net (code "42") (name "Net-(LED8-Pad1)") (class "Default")
      (node (ref "LED8") (pin "1") (pinfunction "1_1") (pintype "passive"))
      (node (ref "R32") (pin "1") (pinfunction "1_1") (pintype "passive"))
    )
  )
)
